# Prototype_1.net
KiCad netlist of a schematic drawn in EAGLE
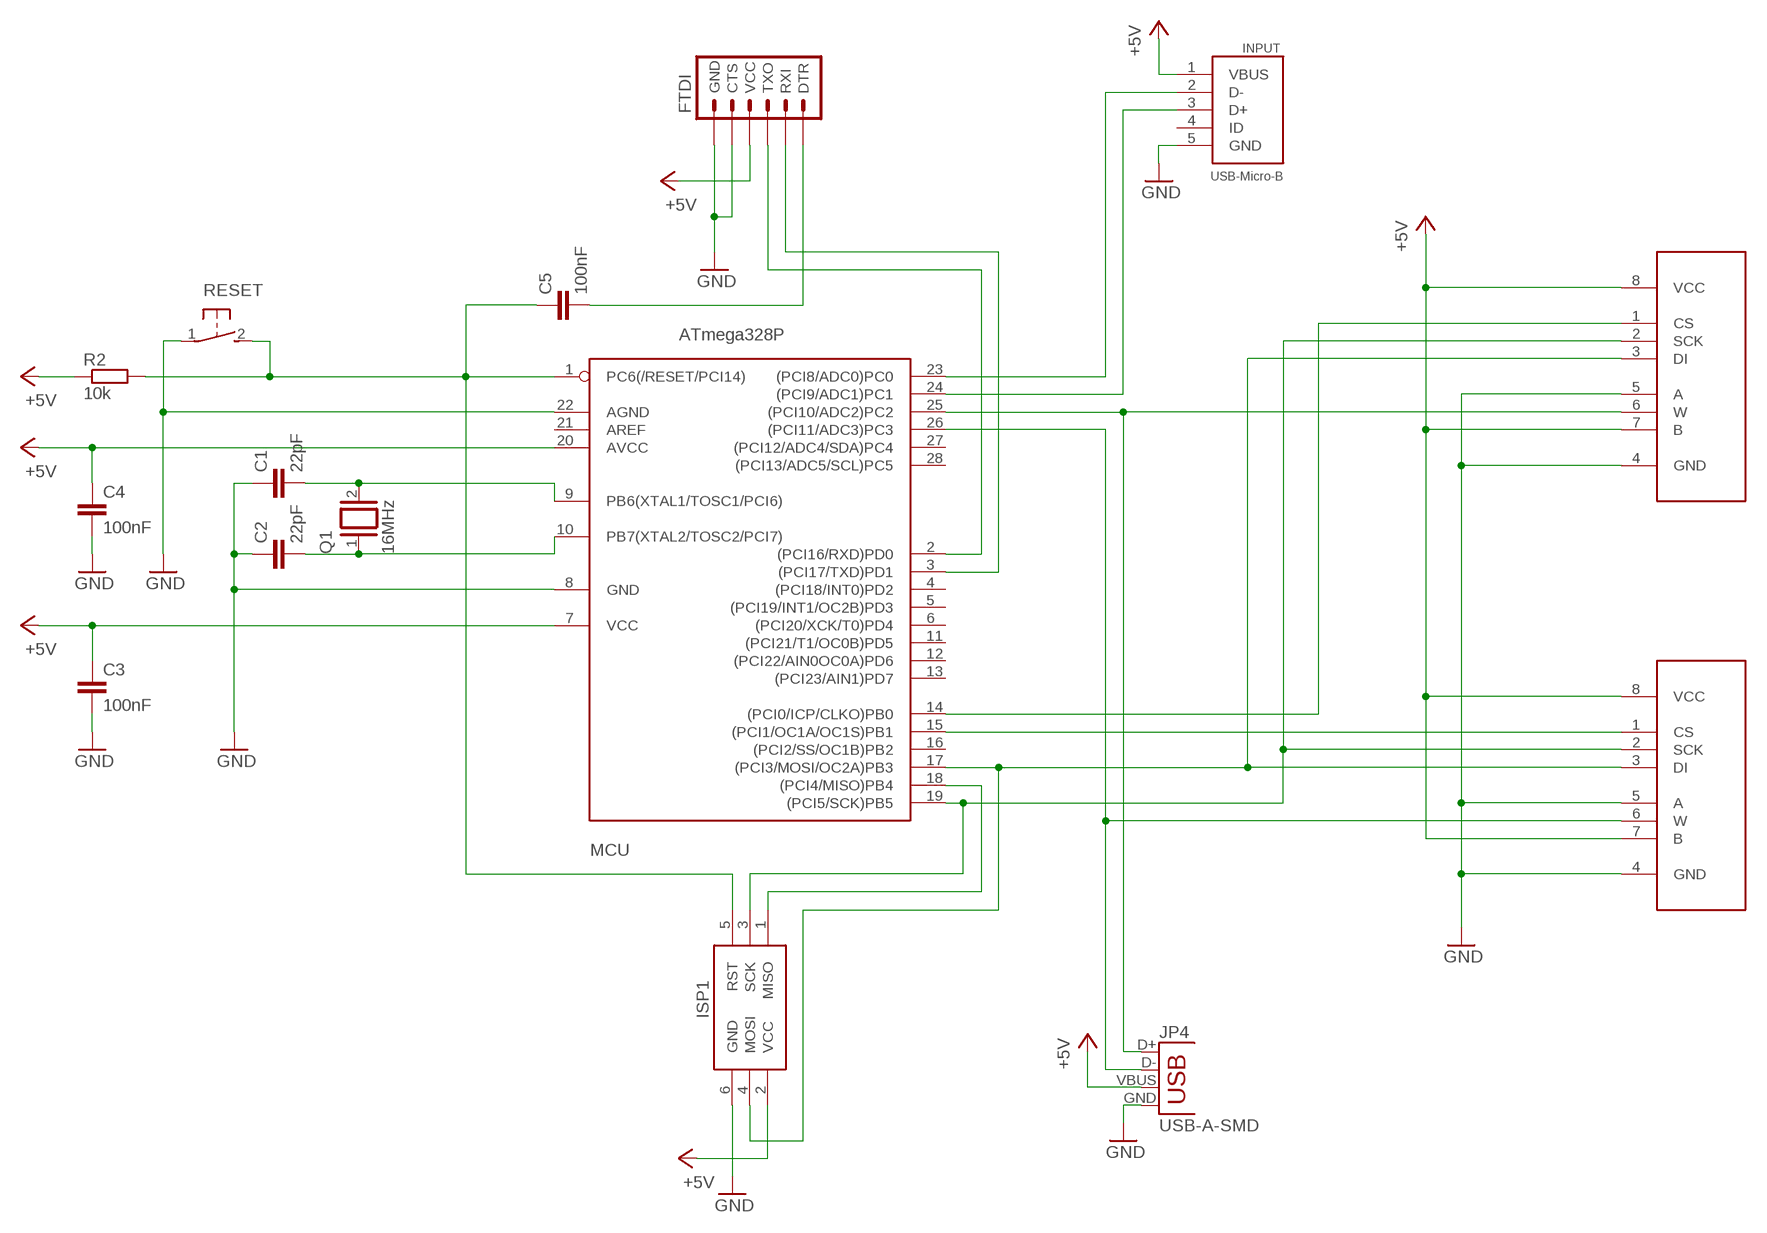
[diagram p0: schematic, sheet 1]

(export (version "E")
  (design (tool "Eeschema 10.0.6"))
  (components
    (comp (ref "C1")
      (value "22pF")
      (footprint "eagle-import:C025-025X050")
      (libsource (lib "eagle-import") (part "resistor_C-EU025-025X050"))
    )
    (comp (ref "C2")
      (value "22pF")
      (footprint "eagle-import:C025-025X050")
      (libsource (lib "eagle-import") (part "resistor_C-EU025-025X050"))
    )
    (comp (ref "C3")
      (value "100nF")
      (footprint "eagle-import:C025-025X050")
      (libsource (lib "eagle-import") (part "C-EU025-025X050"))
    )
    (comp (ref "C4")
      (value "100nF")
      (footprint "eagle-import:C025-025X050")
      (libsource (lib "eagle-import") (part "C-EU025-025X050"))
    )
    (comp (ref "C5")
      (value "100nF")
      (footprint "eagle-import:C025-025X050")
      (libsource (lib "eagle-import") (part "C-EU025-025X050"))
    )
    (comp (ref "FTDI")
      (value "ARDUINO_SERIAL_PROGRAMPTH")
      (footprint "eagle-import:1X06")
      (libsource (lib "eagle-import") (part "ARDUINO_SERIAL_PROGRAMPTH"))
    )
    (comp (ref "INPUT")
      (value "USB-Micro-B")
      (footprint "eagle-import:USB-MICRO-MOLEX-105017-0001")
      (libsource (lib "eagle-import") (part "USB-CON-5PIN-105017-0001"))
    )
    (comp (ref "ISP1")
      (value "AVRISP-6")
      (footprint "eagle-import:AVRISP")
      (libsource (lib "eagle-import") (part "AVRISP-6"))
    )
    (comp (ref "JP4")
      (value "USB-A-SMD")
      (footprint "eagle-import:USB-A-S-NOSILK-FEMALE")
      (libsource (lib "eagle-import") (part "USB-A-SMD"))
    )
    (comp (ref "MCU")
      (value "ATmega328P")
      (footprint "eagle-import:DIL28-3")
      (libsource (lib "eagle-import") (part "ATMEGA168P-20"))
    )
    (comp (ref "POTI")
      (value "MCP41XXXDIL")
      (footprint "eagle-import:DIL-08")
      (libsource (lib "eagle-import") (part "MCP41XXXDIL"))
    )
    (comp (ref "POTI1")
      (value "MCP41XXXDIL")
      (footprint "eagle-import:DIL-08")
      (libsource (lib "eagle-import") (part "MCP41XXXDIL"))
    )
    (comp (ref "Q1")
      (value "16MHz")
      (footprint "eagle-import:Q")
      (libsource (lib "eagle-import") (part "XTAL"))
    )
    (comp (ref "R2")
      (value "10k")
      (footprint "eagle-import:0207_10")
      (libsource (lib "eagle-import") (part "R-EU_0207/10"))
    )
    (comp (ref "RESET")
      (value "31-XX")
      (footprint "eagle-import:B3F-31XX")
      (fields (field (name "MPN") "B3F-3100"))
      (libsource (lib "eagle-import") (part "31-XX"))
    )
  )
  (nets
    (net (code "1") (name "+5V") (class "Default")
      (node (ref "C3") (pin "1") (pinfunction "1_1") (pintype "passive"))
      (node (ref "C4") (pin "1") (pinfunction "1_1") (pintype "passive"))
      (node (ref "FTDI") (pin "4") (pinfunction "VCC_4") (pintype "passive"))
      (node (ref "INPUT") (pin "1") (pinfunction "VBUS_1") (pintype "power_in"))
      (node (ref "ISP1") (pin "2") (pinfunction "VCC_2") (pintype "power_in"))
      (node (ref "JP4") (pin "VBUS") (pinfunction "VBUS_VBUS") (pintype "bidirectional"))
      (node (ref "MCU") (pin "20") (pinfunction "AVCC_20") (pintype "bidirectional"))
      (node (ref "MCU") (pin "7") (pinfunction "VCC_7") (pintype "bidirectional"))
      (node (ref "POTI") (pin "7") (pinfunction "B_7") (pintype "bidirectional"))
      (node (ref "POTI") (pin "8") (pinfunction "VCC_8") (pintype "bidirectional"))
      (node (ref "POTI1") (pin "7") (pinfunction "B_7") (pintype "bidirectional"))
      (node (ref "POTI1") (pin "8") (pinfunction "VCC_8") (pintype "bidirectional"))
      (node (ref "R2") (pin "1") (pinfunction "1_1") (pintype "passive"))
    )
    (net (code "2") (name "GND") (class "Default")
      (node (ref "C1") (pin "1") (pinfunction "1_1") (pintype "passive"))
      (node (ref "C2") (pin "1") (pinfunction "1_1") (pintype "passive"))
      (node (ref "C3") (pin "2") (pinfunction "2_2") (pintype "passive"))
      (node (ref "C4") (pin "2") (pinfunction "2_2") (pintype "passive"))
      (node (ref "FTDI") (pin "5") (pinfunction "CTS_5") (pintype "passive"))
      (node (ref "FTDI") (pin "6") (pinfunction "GND_6") (pintype "passive"))
      (node (ref "INPUT") (pin "5") (pinfunction "GND_5") (pintype "power_in"))
      (node (ref "ISP1") (pin "6") (pinfunction "GND_6") (pintype "power_in"))
      (node (ref "JP4") (pin "GND") (pinfunction "GND_GND") (pintype "bidirectional"))
      (node (ref "MCU") (pin "22") (pinfunction "AGND_22") (pintype "bidirectional"))
      (node (ref "MCU") (pin "8") (pinfunction "GND_8") (pintype "bidirectional"))
      (node (ref "POTI") (pin "4") (pinfunction "GND_4") (pintype "bidirectional"))
      (node (ref "POTI") (pin "5") (pinfunction "A_5") (pintype "bidirectional"))
      (node (ref "POTI1") (pin "4") (pinfunction "GND_4") (pintype "bidirectional"))
      (node (ref "POTI1") (pin "5") (pinfunction "A_5") (pintype "bidirectional"))
      (node (ref "RESET") (pin "1") (pinfunction "P_1") (pintype "passive"))
    )
    (net (code "3") (name "Net-(FTDI-DTR)") (class "Default")
      (node (ref "C5") (pin "2") (pinfunction "2_2") (pintype "passive"))
      (node (ref "FTDI") (pin "1") (pinfunction "DTR_1") (pintype "passive"))
    )
    (net (code "4") (name "Net-(FTDI-RXI)") (class "Default")
      (node (ref "FTDI") (pin "2") (pinfunction "RXI_2") (pintype "passive"))
      (node (ref "MCU") (pin "3") (pinfunction "(PCI17/TXD)PD1_3") (pintype "bidirectional"))
    )
    (net (code "5") (name "Net-(FTDI-TXO)") (class "Default")
      (node (ref "FTDI") (pin "3") (pinfunction "TXO_3") (pintype "passive"))
      (node (ref "MCU") (pin "2") (pinfunction "(PCI16/RXD)PD0_2") (pintype "bidirectional"))
    )
    (net (code "6") (name "Net-(INPUT-D+)") (class "Default")
      (node (ref "INPUT") (pin "3") (pinfunction "D+_3") (pintype "bidirectional"))
      (node (ref "MCU") (pin "24") (pinfunction "(PCI9/ADC1)PC1_24") (pintype "bidirectional"))
    )
    (net (code "7") (name "Net-(INPUT-D-)") (class "Default")
      (node (ref "INPUT") (pin "2") (pinfunction "D-_2") (pintype "bidirectional"))
      (node (ref "MCU") (pin "23") (pinfunction "(PCI8/ADC0)PC0_23") (pintype "bidirectional"))
    )
    (net (code "8") (name "Net-(ISP1-MISO)") (class "Default")
      (node (ref "ISP1") (pin "1") (pinfunction "MISO_1") (pintype "input"))
      (node (ref "MCU") (pin "18") (pinfunction "(PCI4/MISO)PB4_18") (pintype "bidirectional"))
    )
    (net (code "9") (name "Net-(ISP1-MOSI)") (class "Default")
      (node (ref "ISP1") (pin "4") (pinfunction "MOSI_4") (pintype "output"))
      (node (ref "MCU") (pin "17") (pinfunction "(PCI3/MOSI/OC2A)PB3_17") (pintype "bidirectional"))
      (node (ref "POTI") (pin "3") (pinfunction "DI_3") (pintype "bidirectional"))
      (node (ref "POTI1") (pin "3") (pinfunction "DI_3") (pintype "bidirectional"))
    )
    (net (code "10") (name "Net-(ISP1-RST)") (class "Default")
      (node (ref "C5") (pin "1") (pinfunction "1_1") (pintype "passive"))
      (node (ref "ISP1") (pin "5") (pinfunction "RST_5") (pintype "output"))
      (node (ref "MCU") (pin "1") (pinfunction "PC6(/RESET/PCI14)_1") (pintype "bidirectional"))
      (node (ref "R2") (pin "2") (pinfunction "2_2") (pintype "passive"))
      (node (ref "RESET") (pin "2") (pinfunction "S_2") (pintype "passive"))
    )
    (net (code "11") (name "Net-(ISP1-SCK)") (class "Default")
      (node (ref "ISP1") (pin "3") (pinfunction "SCK_3") (pintype "output"))
      (node (ref "MCU") (pin "19") (pinfunction "(PCI5/SCK)PB5_19") (pintype "bidirectional"))
      (node (ref "POTI") (pin "2") (pinfunction "SCK_2") (pintype "bidirectional"))
      (node (ref "POTI1") (pin "2") (pinfunction "SCK_2") (pintype "bidirectional"))
    )
    (net (code "12") (name "Net-(MCU-(PCI0{slash}ICP{slash}CLKO)PB0)") (class "Default")
      (node (ref "MCU") (pin "14") (pinfunction "(PCI0/ICP/CLKO)PB0_14") (pintype "bidirectional"))
      (node (ref "POTI1") (pin "1") (pinfunction "CS_1") (pintype "bidirectional"))
    )
    (net (code "13") (name "Net-(MCU-(PCI1{slash}OC1A{slash}OC1S)PB1)") (class "Default")
      (node (ref "MCU") (pin "15") (pinfunction "(PCI1/OC1A/OC1S)PB1_15") (pintype "bidirectional"))
      (node (ref "POTI") (pin "1") (pinfunction "CS_1") (pintype "bidirectional"))
    )
    (net (code "14") (name "Net-(MCU-(PCI10{slash}ADC2)PC2)") (class "Default")
      (node (ref "JP4") (pin "D+") (pinfunction "D+_D+") (pintype "bidirectional"))
      (node (ref "MCU") (pin "25") (pinfunction "(PCI10/ADC2)PC2_25") (pintype "bidirectional"))
      (node (ref "POTI1") (pin "6") (pinfunction "W_6") (pintype "bidirectional"))
    )
    (net (code "15") (name "Net-(MCU-(PCI11{slash}ADC3)PC3)") (class "Default")
      (node (ref "JP4") (pin "D-") (pinfunction "D-_D-") (pintype "bidirectional"))
      (node (ref "MCU") (pin "26") (pinfunction "(PCI11/ADC3)PC3_26") (pintype "bidirectional"))
      (node (ref "POTI") (pin "6") (pinfunction "W_6") (pintype "bidirectional"))
    )
    (net (code "16") (name "Net-(MCU-PB6(XTAL1{slash}TOSC1{slash}PCI6))") (class "Default")
      (node (ref "C1") (pin "2") (pinfunction "2_2") (pintype "passive"))
      (node (ref "MCU") (pin "9") (pinfunction "PB6(XTAL1/TOSC1/PCI6)_9") (pintype "bidirectional"))
      (node (ref "Q1") (pin "2") (pinfunction "2_2") (pintype "passive"))
    )
    (net (code "17") (name "Net-(MCU-PB7(XTAL2{slash}TOSC2{slash}PCI7))") (class "Default")
      (node (ref "C2") (pin "2") (pinfunction "2_2") (pintype "passive"))
      (node (ref "MCU") (pin "10") (pinfunction "PB7(XTAL2/TOSC2/PCI7)_10") (pintype "bidirectional"))
      (node (ref "Q1") (pin "1") (pinfunction "1_1") (pintype "passive"))
    )
    (net (code "18") (name "unconnected-(INPUT-ID-Pad4)") (class "Default")
      (node (ref "INPUT") (pin "4") (pinfunction "ID_4") (pintype "bidirectional"))
    )
    (net (code "19") (name "unconnected-(MCU-(PCI2{slash}SS{slash}OC1B)PB2-Pad16)") (class "Default")
      (node (ref "MCU") (pin "16") (pinfunction "(PCI2/SS/OC1B)PB2_16") (pintype "bidirectional"))
    )
    (net (code "20") (name "unconnected-(MCU-(PCI12{slash}ADC4{slash}SDA)PC4-Pad27)") (class "Default")
      (node (ref "MCU") (pin "27") (pinfunction "(PCI12/ADC4/SDA)PC4_27") (pintype "bidirectional"))
    )
    (net (code "21") (name "unconnected-(MCU-(PCI13{slash}ADC5{slash}SCL)PC5-Pad28)") (class "Default")
      (node (ref "MCU") (pin "28") (pinfunction "(PCI13/ADC5/SCL)PC5_28") (pintype "bidirectional"))
    )
    (net (code "22") (name "unconnected-(MCU-(PCI18{slash}INT0)PD2-Pad4)") (class "Default")
      (node (ref "MCU") (pin "4") (pinfunction "(PCI18/INT0)PD2_4") (pintype "bidirectional"))
    )
    (net (code "23") (name "unconnected-(MCU-(PCI19{slash}INT1{slash}OC2B)PD3-Pad5)") (class "Default")
      (node (ref "MCU") (pin "5") (pinfunction "(PCI19/INT1/OC2B)PD3_5") (pintype "bidirectional"))
    )
    (net (code "24") (name "unconnected-(MCU-(PCI20{slash}XCK{slash}T0)PD4-Pad6)") (class "Default")
      (node (ref "MCU") (pin "6") (pinfunction "(PCI20/XCK/T0)PD4_6") (pintype "bidirectional"))
    )
    (net (code "25") (name "unconnected-(MCU-(PCI21{slash}T1{slash}OC0B)PD5-Pad11)") (class "Default")
      (node (ref "MCU") (pin "11") (pinfunction "(PCI21/T1/OC0B)PD5_11") (pintype "bidirectional"))
    )
    (net (code "26") (name "unconnected-(MCU-(PCI22{slash}AIN0OC0A)PD6-Pad12)") (class "Default")
      (node (ref "MCU") (pin "12") (pinfunction "(PCI22/AIN0OC0A)PD6_12") (pintype "bidirectional"))
    )
    (net (code "27") (name "unconnected-(MCU-(PCI23{slash}AIN1)PD7-Pad13)") (class "Default")
      (node (ref "MCU") (pin "13") (pinfunction "(PCI23/AIN1)PD7_13") (pintype "bidirectional"))
    )
    (net (code "28") (name "unconnected-(MCU-AREF-Pad21)") (class "Default")
      (node (ref "MCU") (pin "21") (pinfunction "AREF_21") (pintype "bidirectional"))
    )
  )
)
